# espnano.net
KiCad netlist of a schematic drawn in EAGLE
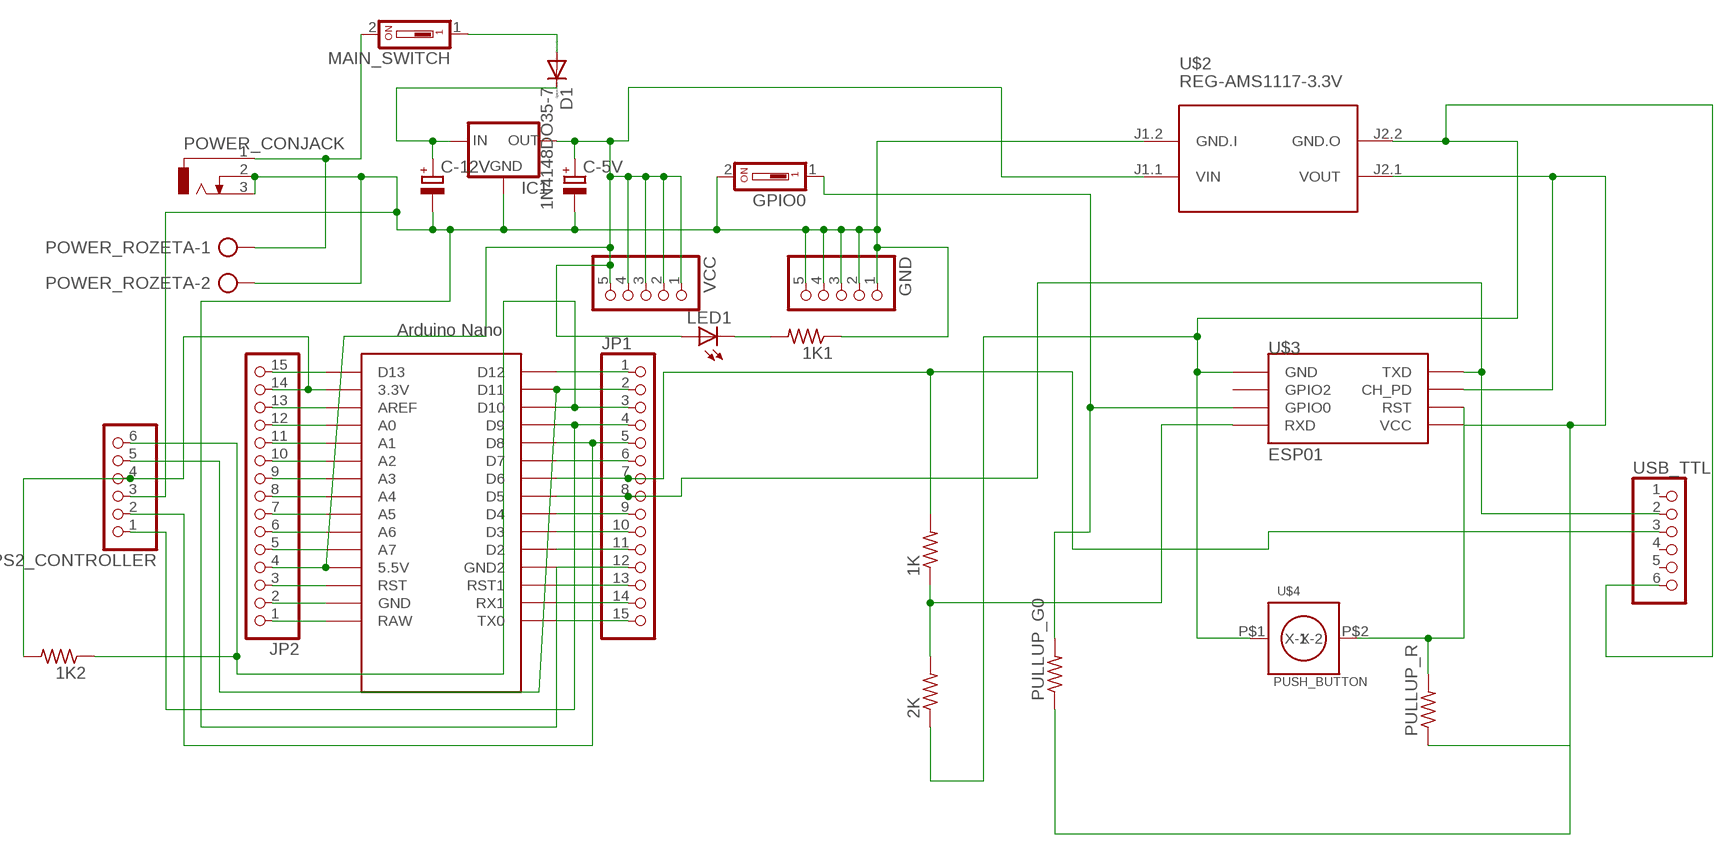
[diagram p0: schematic, sheet 1]

(export (version "E")
  (design (tool "Eeschema 10.0.6"))
  (components
    (comp (ref "1K")
      (value "R-US_0204/7")
      (footprint "eagle-import:0204_7")
      (libsource (lib "eagle-import") (part "R-US_0204/7"))
    )
    (comp (ref "1K1")
      (value "R-US_0204/7")
      (footprint "eagle-import:0204_7")
      (libsource (lib "eagle-import") (part "R-US_0204/7"))
    )
    (comp (ref "1K2")
      (value "R-US_0204/7")
      (footprint "eagle-import:0204_7")
      (libsource (lib "eagle-import") (part "R-US_0204/7"))
    )
    (comp (ref "2K")
      (value "R-US_0204/7")
      (footprint "eagle-import:0204_7")
      (libsource (lib "eagle-import") (part "R-US_0204/7"))
    )
    (comp (ref "C-5V")
      (value "CPOL-EUE2,5-6E")
      (footprint "eagle-import:E2,5-6E")
      (libsource (lib "eagle-import") (part "CPOL-EUE2,5-6E"))
    )
    (comp (ref "C-12V")
      (value "CPOL-EUE2,5-6E")
      (footprint "eagle-import:E2,5-6E")
      (libsource (lib "eagle-import") (part "CPOL-EUE2,5-6E"))
    )
    (comp (ref "D1")
      (value "1N4148DO35-7")
      (footprint "eagle-import:DO35-7")
      (libsource (lib "eagle-import") (part "1N4148DO35-7"))
    )
    (comp (ref "GND")
      (value "PINHD-1X5")
      (footprint "eagle-import:1X05")
      (libsource (lib "eagle-import") (part "PINHD-1X5"))
    )
    (comp (ref "GPIO0")
      (value "DS01")
      (footprint "eagle-import:DS-01")
      (libsource (lib "eagle-import") (part "DS01"))
    )
    (comp (ref "IC1")
      (value "78XXS")
      (footprint "eagle-import:78XXS")
      (libsource (lib "eagle-import") (part "78XXS"))
    )
    (comp (ref "JP1")
      (value "PINHD-1X15")
      (footprint "eagle-import:1X15")
      (libsource (lib "eagle-import") (part "PINHD-1X15"))
    )
    (comp (ref "JP2")
      (value "PINHD-1X15")
      (footprint "eagle-import:1X15")
      (libsource (lib "eagle-import") (part "PINHD-1X15"))
    )
    (comp (ref "LED1")
      (value "LED5MM")
      (footprint "eagle-import:LED5MM")
      (libsource (lib "eagle-import") (part "LED5MM"))
    )
    (comp (ref "MAIN_SWITCH")
      (value "DS01")
      (footprint "eagle-import:DS-01")
      (libsource (lib "eagle-import") (part "DS01"))
    )
    (comp (ref "POWER_CONJACK")
      (value "DCJ0303")
      (footprint "eagle-import:DCJ0303")
      (libsource (lib "eagle-import") (part "DCJ0303"))
    )
    (comp (ref "POWER_ROZETA")
      (value "AK300/2")
      (footprint "eagle-import:AK300_2")
      (libsource (lib "eagle-import") (part "AK300/2"))
    )
    (comp (ref "PS2_CONTROLLER")
      (value "PINHD-1X6")
      (footprint "eagle-import:1X06")
      (libsource (lib "eagle-import") (part "PINHD-1X6"))
    )
    (comp (ref "PULLUP_G0")
      (value "R-US_0204/7")
      (footprint "eagle-import:0204_7")
      (libsource (lib "eagle-import") (part "R-US_0204/7"))
    )
    (comp (ref "PULLUP_R")
      (value "R-US_0204/7")
      (footprint "eagle-import:0204_7")
      (libsource (lib "eagle-import") (part "R-US_0204/7"))
    )
    (comp (ref "U$1")
      (value "NANO")
      (footprint "eagle-import:NANO")
      (libsource (lib "eagle-import") (part "NANO"))
    )
    (comp (ref "U$2")
      (value "REG-AMS1117-3.3V")
      (footprint "eagle-import:REG-AMS1117")
      (libsource (lib "eagle-import") (part "REG-AMS1117-3.3V"))
    )
    (comp (ref "U$3")
      (value "ESP01")
      (footprint "eagle-import:ESP01")
      (libsource (lib "eagle-import") (part "ESP01"))
    )
    (comp (ref "U$4")
      (value "PUSH_BUTTON")
      (footprint "eagle-import:DIP2")
      (libsource (lib "eagle-import") (part "PUSH_BUTTON"))
    )
    (comp (ref "USB_TTL")
      (value "PINHD-1X6")
      (footprint "eagle-import:1X06")
      (libsource (lib "eagle-import") (part "PINHD-1X6"))
    )
    (comp (ref "VCC")
      (value "PINHD-1X5")
      (footprint "eagle-import:1X05")
      (libsource (lib "eagle-import") (part "PINHD-1X5"))
    )
  )
  (nets
    (net (code "1") (name "Net-(1K-Pad2)") (class "Default")
      (node (ref "1K") (pin "2") (pinfunction "2_2") (pintype "passive"))
      (node (ref "JP1") (pin "7") (pinfunction "7_7") (pintype "passive"))
      (node (ref "U$1") (pin "D6") (pinfunction "D6_D6") (pintype "bidirectional"))
      (node (ref "USB_TTL") (pin "3") (pinfunction "3_3") (pintype "passive"))
    )
    (net (code "2") (name "Net-(1K2-Pad1)") (class "Default")
      (node (ref "1K2") (pin "1") (pinfunction "1_1") (pintype "passive"))
      (node (ref "JP1") (pin "3") (pinfunction "3_3") (pintype "passive"))
      (node (ref "PS2_CONTROLLER") (pin "6") (pinfunction "6_6") (pintype "passive"))
      (node (ref "U$1") (pin "D10") (pinfunction "D10_D10") (pintype "bidirectional"))
    )
    (net (code "3") (name "Net-(1K2-Pad2)") (class "Default")
      (node (ref "1K2") (pin "2") (pinfunction "2_2") (pintype "passive"))
      (node (ref "JP2") (pin "14") (pinfunction "14_14") (pintype "passive"))
      (node (ref "PS2_CONTROLLER") (pin "4") (pinfunction "4_4") (pintype "passive"))
      (node (ref "U$1") (pin "3.3V") (pinfunction "3.3V_3.3V") (pintype "bidirectional"))
    )
    (net (code "4") (name "Net-(C-12V-Pad+)") (class "Default")
      (node (ref "C-12V") (pin "+") (pinfunction "+_+") (pintype "passive"))
      (node (ref "D1") (pin "C") (pinfunction "C_C") (pintype "passive"))
      (node (ref "IC1") (pin "IN") (pinfunction "IN_IN") (pintype "input"))
    )
    (net (code "5") (name "Net-(D1-PadA)") (class "Default")
      (node (ref "D1") (pin "A") (pinfunction "A_A") (pintype "passive"))
      (node (ref "MAIN_SWITCH") (pin "1") (pinfunction "1_1") (pintype "passive"))
    )
    (net (code "6") (name "Net-(GPIO0-Pad1)") (class "Default")
      (node (ref "GPIO0") (pin "1") (pinfunction "1_1") (pintype "passive"))
      (node (ref "PULLUP_G0") (pin "2") (pinfunction "2_2") (pintype "passive"))
      (node (ref "U$3") (pin "GPIO0") (pinfunction "GPIO0_GPIO0") (pintype "bidirectional"))
    )
    (net (code "7") (name "Net-(JP1-Pad1)") (class "Default")
      (node (ref "JP1") (pin "1") (pinfunction "1_1") (pintype "passive"))
      (node (ref "U$1") (pin "D12") (pinfunction "D12_D12") (pintype "bidirectional"))
    )
    (net (code "8") (name "Net-(JP1-Pad2)") (class "Default")
      (node (ref "JP1") (pin "2") (pinfunction "2_2") (pintype "passive"))
      (node (ref "PS2_CONTROLLER") (pin "5") (pinfunction "5_5") (pintype "passive"))
      (node (ref "U$1") (pin "D11") (pinfunction "D11_D11") (pintype "bidirectional"))
    )
    (net (code "9") (name "Net-(JP1-Pad4)") (class "Default")
      (node (ref "JP1") (pin "4") (pinfunction "4_4") (pintype "passive"))
      (node (ref "PS2_CONTROLLER") (pin "1") (pinfunction "1_1") (pintype "passive"))
      (node (ref "U$1") (pin "D9") (pinfunction "D9_D9") (pintype "bidirectional"))
    )
    (net (code "10") (name "Net-(JP1-Pad5)") (class "Default")
      (node (ref "JP1") (pin "5") (pinfunction "5_5") (pintype "passive"))
      (node (ref "PS2_CONTROLLER") (pin "2") (pinfunction "2_2") (pintype "passive"))
      (node (ref "U$1") (pin "D8") (pinfunction "D8_D8") (pintype "bidirectional"))
    )
    (net (code "11") (name "Net-(JP1-Pad6)") (class "Default")
      (node (ref "JP1") (pin "6") (pinfunction "6_6") (pintype "passive"))
      (node (ref "U$1") (pin "D7") (pinfunction "D7_D7") (pintype "bidirectional"))
    )
    (net (code "12") (name "Net-(JP1-Pad9)") (class "Default")
      (node (ref "JP1") (pin "9") (pinfunction "9_9") (pintype "passive"))
      (node (ref "U$1") (pin "D4") (pinfunction "D4_D4") (pintype "bidirectional"))
    )
    (net (code "13") (name "Net-(JP1-Pad10)") (class "Default")
      (node (ref "JP1") (pin "10") (pinfunction "10_10") (pintype "passive"))
      (node (ref "U$1") (pin "D3") (pinfunction "D3_D3") (pintype "bidirectional"))
    )
    (net (code "14") (name "Net-(JP1-Pad11)") (class "Default")
      (node (ref "JP1") (pin "11") (pinfunction "11_11") (pintype "passive"))
      (node (ref "U$1") (pin "D2") (pinfunction "D2_D2") (pintype "bidirectional"))
    )
    (net (code "15") (name "Net-(JP1-Pad13)") (class "Default")
      (node (ref "JP1") (pin "13") (pinfunction "13_13") (pintype "passive"))
      (node (ref "U$1") (pin "RST1") (pinfunction "RST1_RST1") (pintype "bidirectional"))
    )
    (net (code "16") (name "Net-(JP1-Pad14)") (class "Default")
      (node (ref "JP1") (pin "14") (pinfunction "14_14") (pintype "passive"))
      (node (ref "U$1") (pin "RX1") (pinfunction "RX1_RX1") (pintype "bidirectional"))
    )
    (net (code "17") (name "Net-(JP1-Pad15)") (class "Default")
      (node (ref "JP1") (pin "15") (pinfunction "15_15") (pintype "passive"))
      (node (ref "U$1") (pin "TX0") (pinfunction "TX0_TX0") (pintype "bidirectional"))
    )
    (net (code "18") (name "Net-(JP2-Pad1)") (class "Default")
      (node (ref "JP2") (pin "1") (pinfunction "1_1") (pintype "passive"))
      (node (ref "U$1") (pin "RAW") (pinfunction "RAW_RAW") (pintype "bidirectional"))
    )
    (net (code "19") (name "Net-(JP2-Pad2)") (class "Default")
      (node (ref "JP2") (pin "2") (pinfunction "2_2") (pintype "passive"))
      (node (ref "U$1") (pin "GND") (pinfunction "GND_GND") (pintype "bidirectional"))
    )
    (net (code "20") (name "Net-(JP2-Pad3)") (class "Default")
      (node (ref "JP2") (pin "3") (pinfunction "3_3") (pintype "passive"))
      (node (ref "U$1") (pin "RST") (pinfunction "RST_RST") (pintype "bidirectional"))
    )
    (net (code "21") (name "Net-(JP2-Pad5)") (class "Default")
      (node (ref "JP2") (pin "5") (pinfunction "5_5") (pintype "passive"))
      (node (ref "U$1") (pin "A7") (pinfunction "A7_A7") (pintype "bidirectional"))
    )
    (net (code "22") (name "Net-(JP2-Pad6)") (class "Default")
      (node (ref "JP2") (pin "6") (pinfunction "6_6") (pintype "passive"))
      (node (ref "U$1") (pin "A6") (pinfunction "A6_A6") (pintype "bidirectional"))
    )
    (net (code "23") (name "Net-(JP2-Pad7)") (class "Default")
      (node (ref "JP2") (pin "7") (pinfunction "7_7") (pintype "passive"))
      (node (ref "U$1") (pin "A5") (pinfunction "A5_A5") (pintype "bidirectional"))
    )
    (net (code "24") (name "Net-(JP2-Pad8)") (class "Default")
      (node (ref "JP2") (pin "8") (pinfunction "8_8") (pintype "passive"))
      (node (ref "U$1") (pin "A4") (pinfunction "A4_A4") (pintype "bidirectional"))
    )
    (net (code "25") (name "Net-(JP2-Pad9)") (class "Default")
      (node (ref "JP2") (pin "9") (pinfunction "9_9") (pintype "passive"))
      (node (ref "U$1") (pin "A3") (pinfunction "A3_A3") (pintype "bidirectional"))
    )
    (net (code "26") (name "Net-(JP2-Pad10)") (class "Default")
      (node (ref "JP2") (pin "10") (pinfunction "10_10") (pintype "passive"))
      (node (ref "U$1") (pin "A2") (pinfunction "A2_A2") (pintype "bidirectional"))
    )
    (net (code "27") (name "Net-(JP2-Pad11)") (class "Default")
      (node (ref "JP2") (pin "11") (pinfunction "11_11") (pintype "passive"))
      (node (ref "U$1") (pin "A1") (pinfunction "A1_A1") (pintype "bidirectional"))
    )
    (net (code "28") (name "Net-(JP2-Pad12)") (class "Default")
      (node (ref "JP2") (pin "12") (pinfunction "12_12") (pintype "passive"))
      (node (ref "U$1") (pin "A0") (pinfunction "A0_A0") (pintype "bidirectional"))
    )
    (net (code "29") (name "Net-(JP2-Pad13)") (class "Default")
      (node (ref "JP2") (pin "13") (pinfunction "13_13") (pintype "passive"))
      (node (ref "U$1") (pin "AREF") (pinfunction "AREF_AREF") (pintype "bidirectional"))
    )
    (net (code "30") (name "Net-(JP2-Pad15)") (class "Default")
      (node (ref "JP2") (pin "15") (pinfunction "15_15") (pintype "passive"))
      (node (ref "U$1") (pin "D13") (pinfunction "D13_D13") (pintype "bidirectional"))
    )
    (net (code "31") (name "Net-(LED1-C)") (class "Default")
      (node (ref "1K1") (pin "2") (pinfunction "2_2") (pintype "passive"))
      (node (ref "LED1") (pin "K") (pinfunction "C_K") (pintype "passive"))
    )
    (net (code "32") (name "Net-(POWER_ROZETAA-KL)") (class "Default")
      (node (ref "MAIN_SWITCH") (pin "2") (pinfunction "2_2") (pintype "passive"))
      (node (ref "POWER_CONJACK") (pin "1") (pinfunction "1_1") (pintype "passive"))
      (node (ref "POWER_ROZETA") (pin "1") (pinfunction "KL_1") (pintype "passive"))
    )
    (net (code "33") (name "Net-(POWER_ROZETAB-KL)") (class "Default")
      (node (ref "1K1") (pin "1") (pinfunction "1_1") (pintype "passive"))
      (node (ref "C-12V") (pin "-") (pinfunction "-_-") (pintype "passive"))
      (node (ref "C-5V") (pin "-") (pinfunction "-_-") (pintype "passive"))
      (node (ref "GND") (pin "1") (pinfunction "1_1") (pintype "passive"))
      (node (ref "GND") (pin "2") (pinfunction "2_2") (pintype "passive"))
      (node (ref "GND") (pin "3") (pinfunction "3_3") (pintype "passive"))
      (node (ref "GND") (pin "4") (pinfunction "4_4") (pintype "passive"))
      (node (ref "GND") (pin "5") (pinfunction "5_5") (pintype "passive"))
      (node (ref "GPIO0") (pin "2") (pinfunction "2_2") (pintype "passive"))
      (node (ref "IC1") (pin "GND") (pinfunction "GND_GND") (pintype "input"))
      (node (ref "JP1") (pin "12") (pinfunction "12_12") (pintype "passive"))
      (node (ref "POWER_CONJACK") (pin "2") (pinfunction "2_2") (pintype "passive"))
      (node (ref "POWER_CONJACK") (pin "3") (pinfunction "3_3") (pintype "passive"))
      (node (ref "POWER_ROZETA") (pin "2") (pinfunction "KL_2") (pintype "passive"))
      (node (ref "PS2_CONTROLLER") (pin "3") (pinfunction "3_3") (pintype "passive"))
      (node (ref "U$1") (pin "GND1") (pinfunction "GND2_GND1") (pintype "bidirectional"))
      (node (ref "U$2") (pin "J1.2") (pinfunction "GND.I_J1.2") (pintype "bidirectional"))
    )
    (net (code "34") (name "Net-(U$1-5.5V)") (class "Default")
      (node (ref "C-5V") (pin "+") (pinfunction "+_+") (pintype "passive"))
      (node (ref "IC1") (pin "OUT") (pinfunction "OUT_OUT") (pintype "passive"))
      (node (ref "JP2") (pin "4") (pinfunction "4_4") (pintype "passive"))
      (node (ref "LED1") (pin "A") (pinfunction "A_A") (pintype "passive"))
      (node (ref "U$1") (pin "5V") (pinfunction "5.5V_5V") (pintype "bidirectional"))
      (node (ref "U$2") (pin "J1.1") (pinfunction "VIN_J1.1") (pintype "bidirectional"))
      (node (ref "VCC") (pin "1") (pinfunction "1_1") (pintype "passive"))
      (node (ref "VCC") (pin "2") (pinfunction "2_2") (pintype "passive"))
      (node (ref "VCC") (pin "3") (pinfunction "3_3") (pintype "passive"))
      (node (ref "VCC") (pin "4") (pinfunction "4_4") (pintype "passive"))
      (node (ref "VCC") (pin "5") (pinfunction "5_5") (pintype "passive"))
    )
    (net (code "35") (name "Net-(U$2-GND.O)") (class "Default")
      (node (ref "2K") (pin "1") (pinfunction "1_1") (pintype "passive"))
      (node (ref "U$2") (pin "J2.2") (pinfunction "GND.O_J2.2") (pintype "bidirectional"))
      (node (ref "U$3") (pin "GND") (pinfunction "GND_GND") (pintype "bidirectional"))
      (node (ref "U$4") (pin "P$1") (pinfunction "X-1_P$1") (pintype "bidirectional"))
      (node (ref "USB_TTL") (pin "6") (pinfunction "6_6") (pintype "passive"))
    )
    (net (code "36") (name "Net-(U$2-VOUT)") (class "Default")
      (node (ref "PULLUP_G0") (pin "1") (pinfunction "1_1") (pintype "passive"))
      (node (ref "PULLUP_R") (pin "1") (pinfunction "1_1") (pintype "passive"))
      (node (ref "U$2") (pin "J2.1") (pinfunction "VOUT_J2.1") (pintype "bidirectional"))
      (node (ref "U$3") (pin "CH_PD") (pinfunction "CH_PD_CH_PD") (pintype "bidirectional"))
      (node (ref "U$3") (pin "VCC") (pinfunction "VCC_VCC") (pintype "bidirectional"))
    )
    (net (code "37") (name "Net-(U$3-RXD)") (class "Default")
      (node (ref "1K") (pin "1") (pinfunction "1_1") (pintype "passive"))
      (node (ref "2K") (pin "2") (pinfunction "2_2") (pintype "passive"))
      (node (ref "U$3") (pin "RX") (pinfunction "RXD_RX") (pintype "bidirectional"))
    )
    (net (code "38") (name "Net-(U$3-TXD)") (class "Default")
      (node (ref "JP1") (pin "8") (pinfunction "8_8") (pintype "passive"))
      (node (ref "U$1") (pin "D5") (pinfunction "D5_D5") (pintype "bidirectional"))
      (node (ref "U$3") (pin "TX") (pinfunction "TXD_TX") (pintype "bidirectional"))
      (node (ref "USB_TTL") (pin "2") (pinfunction "2_2") (pintype "passive"))
    )
    (net (code "39") (name "Net-(U$4-X-2)") (class "Default")
      (node (ref "PULLUP_R") (pin "2") (pinfunction "2_2") (pintype "passive"))
      (node (ref "U$3") (pin "RST") (pinfunction "RST_RST") (pintype "bidirectional"))
      (node (ref "U$4") (pin "P$2") (pinfunction "X-2_P$2") (pintype "bidirectional"))
    )
    (net (code "40") (name "unconnected-(U$3-PadGPIO2)") (class "Default")
      (node (ref "U$3") (pin "GPIO2") (pinfunction "GPIO2_GPIO2") (pintype "bidirectional"))
    )
    (net (code "41") (name "unconnected-(USB_TTL-Pad1)") (class "Default")
      (node (ref "USB_TTL") (pin "1") (pinfunction "1_1") (pintype "passive"))
    )
    (net (code "42") (name "unconnected-(USB_TTL-Pad4)") (class "Default")
      (node (ref "USB_TTL") (pin "4") (pinfunction "4_4") (pintype "passive"))
    )
    (net (code "43") (name "unconnected-(USB_TTL-Pad5)") (class "Default")
      (node (ref "USB_TTL") (pin "5") (pinfunction "5_5") (pintype "passive"))
    )
  )
)
